# ESPLiveDC.net
KiCad netlist of a schematic drawn in EAGLE
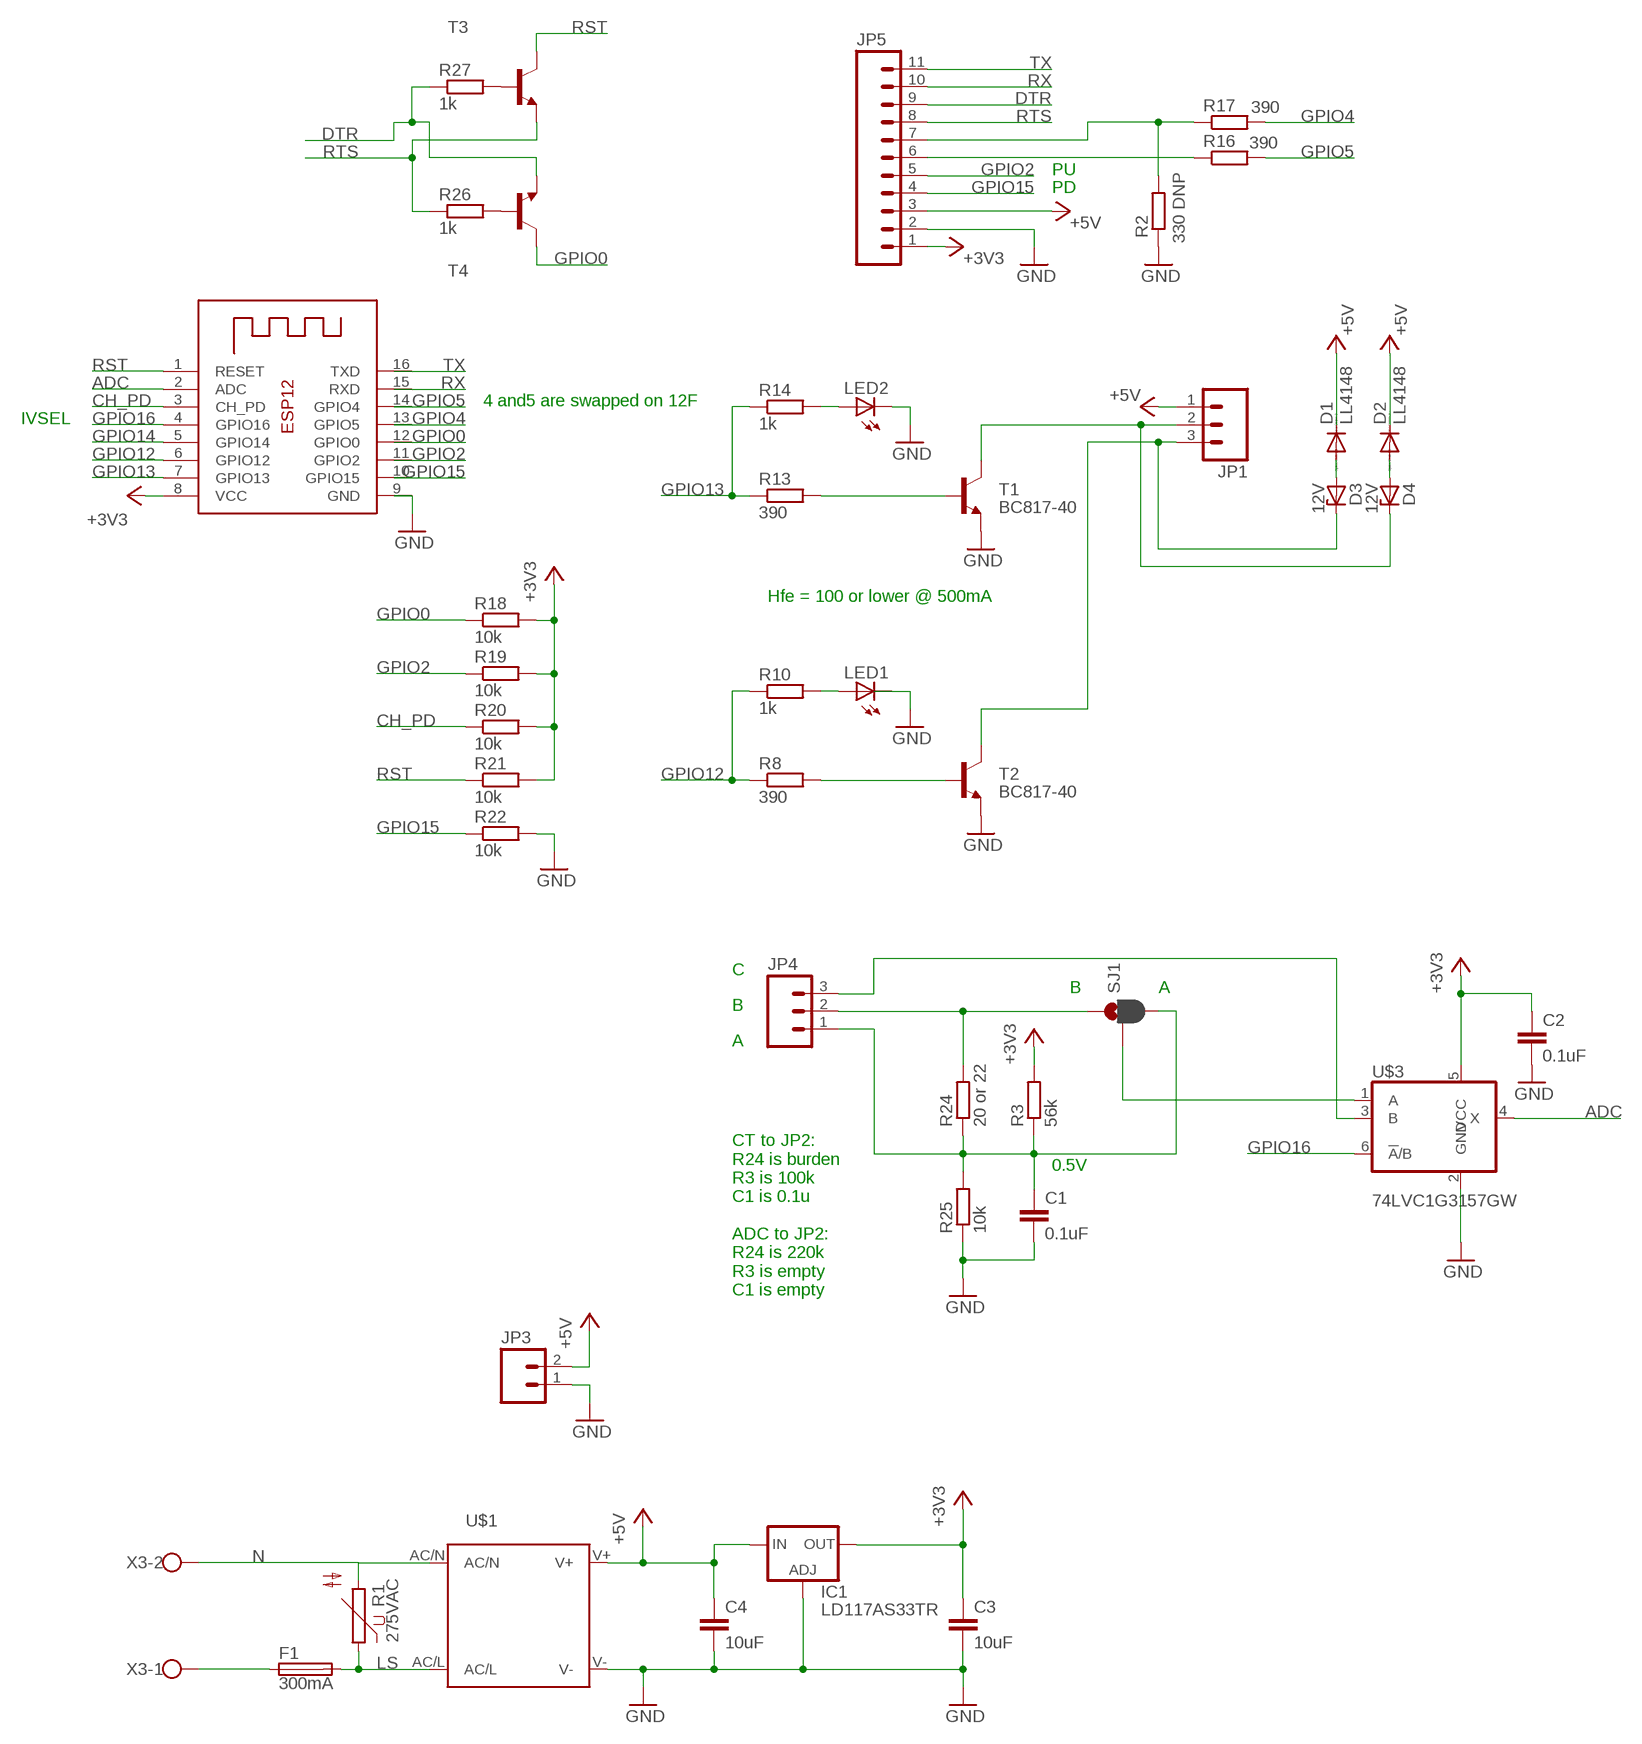
[diagram p0: schematic, sheet 1]

(export (version "E")
  (design (tool "Eeschema 10.0.6"))
  (components
    (comp (ref "C1")
      (value "0.1uF")
      (footprint "eagle-import:C0603")
      (libsource (lib "eagle-import") (part "C-EUC0603"))
    )
    (comp (ref "C2")
      (value "0.1uF")
      (footprint "eagle-import:C0603")
      (libsource (lib "eagle-import") (part "C-EUC0603"))
    )
    (comp (ref "C3")
      (value "10uF")
      (footprint "eagle-import:C0805")
      (libsource (lib "eagle-import") (part "C-EUC0805"))
    )
    (comp (ref "C4")
      (value "10uF")
      (footprint "eagle-import:C0805")
      (libsource (lib "eagle-import") (part "C-EUC0805"))
    )
    (comp (ref "D1")
      (value "LL4148")
      (footprint "eagle-import:SOD80C")
      (libsource (lib "eagle-import") (part "DIODE-SOD80C"))
    )
    (comp (ref "D2")
      (value "LL4148")
      (footprint "eagle-import:SOD80C")
      (libsource (lib "eagle-import") (part "DIODE-SOD80C"))
    )
    (comp (ref "D3")
      (value "12V")
      (footprint "eagle-import:SOD80C")
      (libsource (lib "eagle-import") (part "ZENER-DIODESOD80C"))
    )
    (comp (ref "D4")
      (value "12V")
      (footprint "eagle-import:SOD80C")
      (libsource (lib "eagle-import") (part "ZENER-DIODESOD80C"))
    )
    (comp (ref "F1")
      (value "300mA")
      (footprint "eagle-import:TE5")
      (libsource (lib "eagle-import") (part "TE5"))
    )
    (comp (ref "IC1")
      (value "LD117AS33TR")
      (footprint "eagle-import:SOT223")
      (libsource (lib "eagle-import") (part "LD117A?S33TR"))
    )
    (comp (ref "JP1")
      (value "M03POLAR_LOCK")
      (footprint "eagle-import:MOLEX-1X3_LOCK")
      (libsource (lib "eagle-import") (part "M03POLAR_LOCK"))
    )
    (comp (ref "JP3")
      (value "M02POLAR_LOCK")
      (footprint "eagle-import:MOLEX-1X2_LOCK")
      (libsource (lib "eagle-import") (part "M02POLAR_LOCK"))
    )
    (comp (ref "JP4")
      (value "M03POLAR_LOCK")
      (footprint "eagle-import:MOLEX-1X3_LOCK")
      (libsource (lib "eagle-import") (part "M03POLAR_LOCK"))
    )
    (comp (ref "JP5")
      (value "M11LOCK")
      (footprint "eagle-import:1X11_LOCK")
      (libsource (lib "eagle-import") (part "M11LOCK"))
    )
    (comp (ref "LED1")
      (value "LED1206")
      (footprint "eagle-import:LED-1206")
      (libsource (lib "eagle-import") (part "LED1206"))
    )
    (comp (ref "LED2")
      (value "LED1206")
      (footprint "eagle-import:LED-1206")
      (libsource (lib "eagle-import") (part "LED1206"))
    )
    (comp (ref "R1")
      (value "275VAC")
      (footprint "eagle-import:P593")
      (libsource (lib "eagle-import") (part "P593"))
    )
    (comp (ref "R2")
      (value "330 DNP")
      (footprint "eagle-import:R0603")
      (libsource (lib "eagle-import") (part "R-EU_R0603"))
    )
    (comp (ref "R3")
      (value "56k")
      (footprint "eagle-import:R0603")
      (libsource (lib "eagle-import") (part "R-EU_R0603"))
    )
    (comp (ref "R8")
      (value "390")
      (footprint "eagle-import:R0603")
      (libsource (lib "eagle-import") (part "R-EU_R0603"))
    )
    (comp (ref "R10")
      (value "1k")
      (footprint "eagle-import:R0603")
      (libsource (lib "eagle-import") (part "R-EU_R0603"))
    )
    (comp (ref "R13")
      (value "390")
      (footprint "eagle-import:R0603")
      (libsource (lib "eagle-import") (part "R-EU_R0603"))
    )
    (comp (ref "R14")
      (value "1k")
      (footprint "eagle-import:R0603")
      (libsource (lib "eagle-import") (part "R-EU_R0603"))
    )
    (comp (ref "R16")
      (value "390")
      (footprint "eagle-import:R0603")
      (libsource (lib "eagle-import") (part "R-EU_R0603"))
    )
    (comp (ref "R17")
      (value "390")
      (footprint "eagle-import:R0603")
      (libsource (lib "eagle-import") (part "R-EU_R0603"))
    )
    (comp (ref "R18")
      (value "10k")
      (footprint "eagle-import:R0603")
      (libsource (lib "eagle-import") (part "R-EU_R0603"))
    )
    (comp (ref "R19")
      (value "10k")
      (footprint "eagle-import:R0603")
      (libsource (lib "eagle-import") (part "R-EU_R0603"))
    )
    (comp (ref "R20")
      (value "10k")
      (footprint "eagle-import:R0603")
      (libsource (lib "eagle-import") (part "R-EU_R0603"))
    )
    (comp (ref "R21")
      (value "10k")
      (footprint "eagle-import:R0603")
      (libsource (lib "eagle-import") (part "R-EU_R0603"))
    )
    (comp (ref "R22")
      (value "10k")
      (footprint "eagle-import:R0603")
      (libsource (lib "eagle-import") (part "R-EU_R0603"))
    )
    (comp (ref "R24")
      (value "20 or 22")
      (footprint "eagle-import:R1206")
      (libsource (lib "eagle-import") (part "R-EU_R1206"))
    )
    (comp (ref "R25")
      (value "10k")
      (footprint "eagle-import:R0603")
      (libsource (lib "eagle-import") (part "R-EU_R0603"))
    )
    (comp (ref "R26")
      (value "1k")
      (footprint "eagle-import:R0603")
      (libsource (lib "eagle-import") (part "R-EU_R0603"))
    )
    (comp (ref "R27")
      (value "1k")
      (footprint "eagle-import:R0603")
      (libsource (lib "eagle-import") (part "R-EU_R0603"))
    )
    (comp (ref "SJ1")
      (value "JUMPER-PAD-3-2OF3_NC_BY_PASTE")
      (footprint "eagle-import:PAD-JUMPER-3-2OF3_NC_BY_PASTE_YES_SILK_FULL_BOX")
      (libsource (lib "eagle-import") (part "JUMPER-PAD-3-2OF3_NC_BY_PASTE"))
    )
    (comp (ref "T1")
      (value "BC817-40")
      (footprint "eagle-import:SOT23-BEC")
      (libsource (lib "eagle-import") (part "-NPN-SOT23-BECBC817-40"))
    )
    (comp (ref "T2")
      (value "BC817-40")
      (footprint "eagle-import:SOT23-BEC")
      (libsource (lib "eagle-import") (part "-NPN-SOT23-BECBC817-40"))
    )
    (comp (ref "T3")
      (value "BC817-40-NPN-SOT23-BEC")
      (footprint "eagle-import:SOT23-BEC")
      (libsource (lib "eagle-import") (part "-NPN-SOT23-BECBC817-40"))
    )
    (comp (ref "T4")
      (value "BC817-40-NPN-SOT23-BEC")
      (footprint "eagle-import:SOT23-BEC")
      (libsource (lib "eagle-import") (part "-NPN-SOT23-BECBC817-40"))
    )
    (comp (ref "U$1")
      (value "IRM_01/02_SMDIRM_01/02_SMD")
      (footprint "eagle-import:IRM_01_02_SMD")
      (libsource (lib "eagle-import") (part "IRM_01/02_SMDIRM_01/02_SMD"))
    )
    (comp (ref "U$3")
      (value "74LVC1G3157GW")
      (footprint "eagle-import:SOT363")
      (libsource (lib "eagle-import") (part "74LVC1G3157GW"))
    )
    (comp (ref "X1")
      (value "ESP-12")
      (footprint "eagle-import:ESP-12")
      (libsource (lib "eagle-import") (part "ESP-12"))
    )
    (comp (ref "X3")
      (value "W237-102")
      (footprint "eagle-import:W237-102")
      (fields (field (name "MPN") "237-102"))
      (libsource (lib "eagle-import") (part "W237-102"))
    )
  )
  (nets
    (net (code "1") (name "+3V3") (class "Default")
      (node (ref "C2") (pin "1") (pinfunction "1_1") (pintype "passive"))
      (node (ref "C3") (pin "1") (pinfunction "1_1") (pintype "passive"))
      (node (ref "IC1") (pin "4") (pinfunction "OUT_4") (pintype "passive"))
      (node (ref "JP5") (pin "1") (pinfunction "1_1") (pintype "passive"))
      (node (ref "R18") (pin "2") (pinfunction "2_2") (pintype "passive"))
      (node (ref "R19") (pin "2") (pinfunction "2_2") (pintype "passive"))
      (node (ref "R20") (pin "2") (pinfunction "2_2") (pintype "passive"))
      (node (ref "R21") (pin "2") (pinfunction "2_2") (pintype "passive"))
      (node (ref "R3") (pin "2") (pinfunction "2_2") (pintype "passive"))
      (node (ref "U$3") (pin "5") (pinfunction "VCC_5") (pintype "power_in"))
      (node (ref "X1") (pin "8") (pinfunction "VCC_8") (pintype "power_in"))
    )
    (net (code "2") (name "+5V") (class "Default")
      (node (ref "C4") (pin "1") (pinfunction "1_1") (pintype "passive"))
      (node (ref "D1") (pin "C") (pinfunction "C_C") (pintype "passive"))
      (node (ref "D2") (pin "C") (pinfunction "C_C") (pintype "passive"))
      (node (ref "IC1") (pin "3") (pinfunction "IN_3") (pintype "input"))
      (node (ref "JP1") (pin "1") (pinfunction "1_1") (pintype "passive"))
      (node (ref "JP3") (pin "2") (pinfunction "2_2") (pintype "passive"))
      (node (ref "JP5") (pin "3") (pinfunction "3_3") (pintype "passive"))
      (node (ref "U$1") (pin "V+") (pinfunction "V+_V+") (pintype "output"))
    )
    (net (code "3") (name "/ADC") (class "Default")
      (node (ref "U$3") (pin "4") (pinfunction "X_4") (pintype "bidirectional"))
      (node (ref "X1") (pin "2") (pinfunction "ADC_2") (pintype "passive"))
    )
    (net (code "4") (name "/CH_PD") (class "Default")
      (node (ref "R20") (pin "1") (pinfunction "1_1") (pintype "passive"))
      (node (ref "X1") (pin "3") (pinfunction "CH_PD_3") (pintype "input"))
    )
    (net (code "5") (name "/DTR") (class "Default")
      (node (ref "JP5") (pin "9") (pinfunction "9_9") (pintype "passive"))
      (node (ref "R27") (pin "1") (pinfunction "1_1") (pintype "passive"))
      (node (ref "T4") (pin "E") (pinfunction "E_E") (pintype "passive"))
    )
    (net (code "6") (name "/GPIO0") (class "Default")
      (node (ref "R18") (pin "1") (pinfunction "1_1") (pintype "passive"))
      (node (ref "T4") (pin "C") (pinfunction "C_C") (pintype "passive"))
      (node (ref "X1") (pin "12") (pinfunction "GPIO0_12") (pintype "bidirectional"))
    )
    (net (code "7") (name "/GPIO2") (class "Default")
      (node (ref "JP5") (pin "5") (pinfunction "5_5") (pintype "passive"))
      (node (ref "R19") (pin "1") (pinfunction "1_1") (pintype "passive"))
      (node (ref "X1") (pin "11") (pinfunction "GPIO2_11") (pintype "bidirectional"))
    )
    (net (code "8") (name "/GPIO4") (class "Default")
      (node (ref "R17") (pin "2") (pinfunction "2_2") (pintype "passive"))
      (node (ref "X1") (pin "13") (pinfunction "GPIO5_13") (pintype "bidirectional"))
    )
    (net (code "9") (name "/GPIO5") (class "Default")
      (node (ref "R16") (pin "2") (pinfunction "2_2") (pintype "passive"))
      (node (ref "X1") (pin "14") (pinfunction "GPIO4_14") (pintype "bidirectional"))
    )
    (net (code "10") (name "/GPIO12") (class "Default")
      (node (ref "R10") (pin "1") (pinfunction "1_1") (pintype "passive"))
      (node (ref "R8") (pin "1") (pinfunction "1_1") (pintype "passive"))
      (node (ref "X1") (pin "6") (pinfunction "GPIO12_6") (pintype "bidirectional"))
    )
    (net (code "11") (name "/GPIO13") (class "Default")
      (node (ref "R13") (pin "1") (pinfunction "1_1") (pintype "passive"))
      (node (ref "R14") (pin "1") (pinfunction "1_1") (pintype "passive"))
      (node (ref "X1") (pin "7") (pinfunction "GPIO13_7") (pintype "bidirectional"))
    )
    (net (code "12") (name "/GPIO14") (class "Default")
      (node (ref "X1") (pin "5") (pinfunction "GPIO14_5") (pintype "bidirectional"))
    )
    (net (code "13") (name "/GPIO15") (class "Default")
      (node (ref "JP5") (pin "4") (pinfunction "4_4") (pintype "passive"))
      (node (ref "R22") (pin "1") (pinfunction "1_1") (pintype "passive"))
      (node (ref "X1") (pin "10") (pinfunction "GPIO15_10") (pintype "bidirectional"))
    )
    (net (code "14") (name "/GPIO16") (class "Default")
      (node (ref "U$3") (pin "6") (pinfunction "~{A}/B_6") (pintype "input"))
      (node (ref "X1") (pin "4") (pinfunction "GPIO16_4") (pintype "bidirectional"))
    )
    (net (code "15") (name "/LS") (class "Default")
      (node (ref "F1") (pin "2") (pinfunction "2_2") (pintype "passive"))
      (node (ref "R1") (pin "1") (pinfunction "1_1") (pintype "passive"))
      (node (ref "U$1") (pin "AC/L") (pinfunction "AC/L_AC/L") (pintype "input"))
    )
    (net (code "16") (name "/N") (class "Default")
      (node (ref "R1") (pin "2") (pinfunction "2_2") (pintype "passive"))
      (node (ref "U$1") (pin "AC/N") (pinfunction "AC/N_AC/N") (pintype "input"))
      (node (ref "X3") (pin "2") (pinfunction "KL_2") (pintype "passive"))
    )
    (net (code "17") (name "/RST") (class "Default")
      (node (ref "R21") (pin "1") (pinfunction "1_1") (pintype "passive"))
      (node (ref "T3") (pin "C") (pinfunction "C_C") (pintype "passive"))
      (node (ref "X1") (pin "1") (pinfunction "RESET_1") (pintype "input"))
    )
    (net (code "18") (name "/RTS") (class "Default")
      (node (ref "JP5") (pin "8") (pinfunction "8_8") (pintype "passive"))
      (node (ref "R26") (pin "1") (pinfunction "1_1") (pintype "passive"))
      (node (ref "T3") (pin "E") (pinfunction "E_E") (pintype "passive"))
    )
    (net (code "19") (name "/RX") (class "Default")
      (node (ref "JP5") (pin "10") (pinfunction "10_10") (pintype "passive"))
      (node (ref "X1") (pin "15") (pinfunction "RXD_15") (pintype "input"))
    )
    (net (code "20") (name "/TX") (class "Default")
      (node (ref "JP5") (pin "11") (pinfunction "11_11") (pintype "passive"))
      (node (ref "X1") (pin "16") (pinfunction "TXD_16") (pintype "output"))
    )
    (net (code "21") (name "GND") (class "Default")
      (node (ref "C1") (pin "2") (pinfunction "2_2") (pintype "passive"))
      (node (ref "C2") (pin "2") (pinfunction "2_2") (pintype "passive"))
      (node (ref "C3") (pin "2") (pinfunction "2_2") (pintype "passive"))
      (node (ref "C4") (pin "2") (pinfunction "2_2") (pintype "passive"))
      (node (ref "IC1") (pin "1") (pinfunction "ADJ_1") (pintype "input"))
      (node (ref "JP3") (pin "1") (pinfunction "1_1") (pintype "passive"))
      (node (ref "JP5") (pin "2") (pinfunction "2_2") (pintype "passive"))
      (node (ref "LED1") (pin "C") (pinfunction "C_C") (pintype "passive"))
      (node (ref "LED2") (pin "C") (pinfunction "C_C") (pintype "passive"))
      (node (ref "R2") (pin "1") (pinfunction "1_1") (pintype "passive"))
      (node (ref "R22") (pin "2") (pinfunction "2_2") (pintype "passive"))
      (node (ref "R25") (pin "1") (pinfunction "1_1") (pintype "passive"))
      (node (ref "T1") (pin "E") (pinfunction "E_E") (pintype "passive"))
      (node (ref "T2") (pin "E") (pinfunction "E_E") (pintype "passive"))
      (node (ref "U$1") (pin "V-") (pinfunction "V-_V-") (pintype "output"))
      (node (ref "U$3") (pin "2") (pinfunction "GND_2") (pintype "power_in"))
      (node (ref "X1") (pin "9") (pinfunction "GND_9") (pintype "power_in"))
    )
    (net (code "22") (name "Net-(C1-Pad1)") (class "Default")
      (node (ref "C1") (pin "1") (pinfunction "1_1") (pintype "passive"))
      (node (ref "JP4") (pin "1") (pinfunction "1_1") (pintype "passive"))
      (node (ref "R24") (pin "1") (pinfunction "1_1") (pintype "passive"))
      (node (ref "R25") (pin "2") (pinfunction "2_2") (pintype "passive"))
      (node (ref "R3") (pin "1") (pinfunction "1_1") (pintype "passive"))
      (node (ref "SJ1") (pin "3") (pinfunction "3_3") (pintype "passive"))
    )
    (net (code "23") (name "Net-(D1-PadA)") (class "Default")
      (node (ref "D1") (pin "A") (pinfunction "A_A") (pintype "passive"))
      (node (ref "D3") (pin "A") (pinfunction "A_A") (pintype "passive"))
    )
    (net (code "24") (name "Net-(D2-PadA)") (class "Default")
      (node (ref "D2") (pin "A") (pinfunction "A_A") (pintype "passive"))
      (node (ref "D4") (pin "A") (pinfunction "A_A") (pintype "passive"))
    )
    (net (code "25") (name "Net-(D3-PadC)") (class "Default")
      (node (ref "D3") (pin "C") (pinfunction "C_C") (pintype "passive"))
      (node (ref "JP1") (pin "3") (pinfunction "3_3") (pintype "passive"))
      (node (ref "T2") (pin "C") (pinfunction "C_C") (pintype "passive"))
    )
    (net (code "26") (name "Net-(D4-PadC)") (class "Default")
      (node (ref "D4") (pin "C") (pinfunction "C_C") (pintype "passive"))
      (node (ref "JP1") (pin "2") (pinfunction "2_2") (pintype "passive"))
      (node (ref "T1") (pin "C") (pinfunction "C_C") (pintype "passive"))
    )
    (net (code "27") (name "Net-(JP4-Pad2)") (class "Default")
      (node (ref "JP4") (pin "2") (pinfunction "2_2") (pintype "passive"))
      (node (ref "R24") (pin "2") (pinfunction "2_2") (pintype "passive"))
      (node (ref "SJ1") (pin "1") (pinfunction "1_1") (pintype "passive"))
    )
    (net (code "28") (name "Net-(JP5-Pad6)") (class "Default")
      (node (ref "JP5") (pin "6") (pinfunction "6_6") (pintype "passive"))
      (node (ref "R16") (pin "1") (pinfunction "1_1") (pintype "passive"))
    )
    (net (code "29") (name "Net-(JP5-Pad7)") (class "Default")
      (node (ref "JP5") (pin "7") (pinfunction "7_7") (pintype "passive"))
      (node (ref "R17") (pin "1") (pinfunction "1_1") (pintype "passive"))
      (node (ref "R2") (pin "2") (pinfunction "2_2") (pintype "passive"))
    )
    (net (code "30") (name "Net-(LED1-PadA)") (class "Default")
      (node (ref "LED1") (pin "A") (pinfunction "A_A") (pintype "passive"))
      (node (ref "R10") (pin "2") (pinfunction "2_2") (pintype "passive"))
    )
    (net (code "31") (name "Net-(LED2-PadA)") (class "Default")
      (node (ref "LED2") (pin "A") (pinfunction "A_A") (pintype "passive"))
      (node (ref "R14") (pin "2") (pinfunction "2_2") (pintype "passive"))
    )
    (net (code "32") (name "Net-(R8-Pad2)") (class "Default")
      (node (ref "R8") (pin "2") (pinfunction "2_2") (pintype "passive"))
      (node (ref "T2") (pin "B") (pinfunction "B_B") (pintype "passive"))
    )
    (net (code "33") (name "Net-(R13-Pad2)") (class "Default")
      (node (ref "R13") (pin "2") (pinfunction "2_2") (pintype "passive"))
      (node (ref "T1") (pin "B") (pinfunction "B_B") (pintype "passive"))
    )
    (net (code "34") (name "Net-(R26-Pad2)") (class "Default")
      (node (ref "R26") (pin "2") (pinfunction "2_2") (pintype "passive"))
      (node (ref "T4") (pin "B") (pinfunction "B_B") (pintype "passive"))
    )
    (net (code "35") (name "Net-(R27-Pad2)") (class "Default")
      (node (ref "R27") (pin "2") (pinfunction "2_2") (pintype "passive"))
      (node (ref "T3") (pin "B") (pinfunction "B_B") (pintype "passive"))
    )
    (net (code "36") (name "Net-(U$3-A)") (class "Default")
      (node (ref "SJ1") (pin "2") (pinfunction "2_2") (pintype "passive"))
      (node (ref "U$3") (pin "1") (pinfunction "A_1") (pintype "bidirectional"))
    )
    (net (code "37") (name "Net-(U$3-B)") (class "Default")
      (node (ref "JP4") (pin "3") (pinfunction "3_3") (pintype "passive"))
      (node (ref "U$3") (pin "3") (pinfunction "B_3") (pintype "bidirectional"))
    )
    (net (code "38") (name "Net-(X3A-KL)") (class "Default")
      (node (ref "F1") (pin "1") (pinfunction "1_1") (pintype "passive"))
      (node (ref "X3") (pin "1") (pinfunction "KL_1") (pintype "passive"))
    )
  )
)
